# RF_wireless.net
KiCad netlist of a schematic drawn in Altium Designer
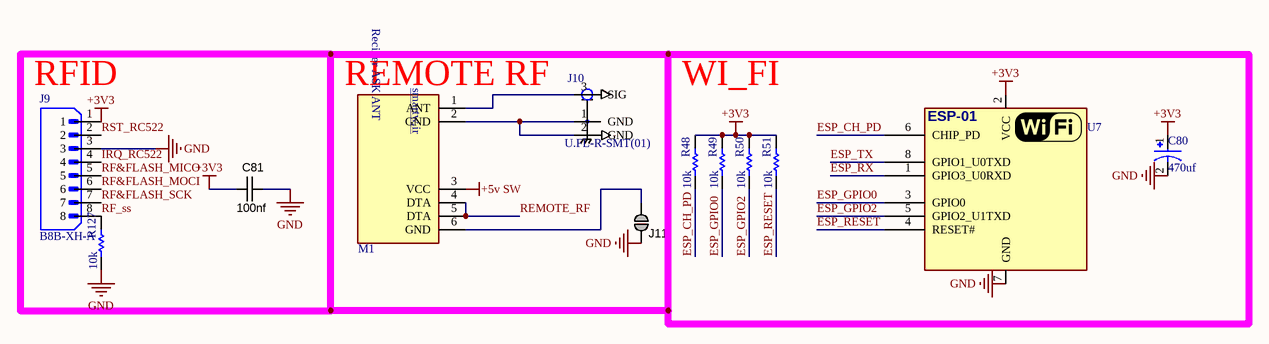
[diagram p0: RF & wireless.SchDoc]

(export (version "E")
  (design (tool "Eeschema 10.0.6"))
  (components
    (comp (ref "C80")
      (value "470uf")
      (footprint "CAP_4TPB330ML")
      (fields (field (name "MP") "4TPB330ML") (field (name "MF") "Sanyo Electric"))
      (libsource (lib "altium-import") (part "root_3_4TPB330ML_"))
    )
    (comp (ref "C81")
      (value "100nf")
      (footprint "CAPC1608X90N")
      (description "Capacitor SMD Cer 100nF 10% 50V X7R 0603")
      (fields (field (name "TOLERANCE") "±10%"))
      (libsource (lib "altium-import") (part "root_1_CAPC_100n_0603_X7R_50V_10%_"))
    )
    (comp (ref "J9")
      (value "B8B-XH-A")
      (footprint "JST_B8B-XH-A")
      (description "Connector Header Through Hole 8 position 0.098 (2.50mm)")
      (fields (field (name "MF") "JST"))
      (libsource (lib "B8B-XH-A") (part "B8B-XH-A"))
    )
    (comp (ref "J10")
      (value "U.FL-R-SMT(01)")
      (footprint "UFL")
      (description "U.FL Series 6 Ghz 50 Ohm Ultra-small SMT Coaxial Cable Receptacle")
      (fields (field (name "MF") "Hirose"))
      (libsource (lib "U.FL-R-SMT_01_") (part "U.FL-R-SMT(01)"))
    )
    (comp (ref "J11")
      (value "Jumper")
      (footprint "JUMP1")
      (description "SMD jumper")
      (libsource (lib "Utiliti_Library") (part "JUMP1"))
    )
    (comp (ref "M1")
      (value "ASK RF ANT 315/433MHZ")
      (footprint "RF_ETRXB")
      (libsource (lib "Module") (part "ASK RF ANT 315/433MHZ"))
    )
    (comp (ref "R48")
      (value "10k")
      (footprint "Resistor_SMD_0603 (1608)")
      (description "Resistor 0603")
      (fields (field (name "PUBLISHER") "Seyed Razi Vesali") (field (name "EMAIL") "razi.vesali@gmail.com"))
      (libsource (lib "resistors") (part "Resistor"))
    )
    (comp (ref "R49")
      (value "10k")
      (footprint "Resistor_SMD_0603 (1608)")
      (description "Resistor 0603")
      (fields (field (name "PUBLISHER") "Seyed Razi Vesali") (field (name "EMAIL") "razi.vesali@gmail.com"))
      (libsource (lib "resistors") (part "Resistor"))
    )
    (comp (ref "R50")
      (value "10k")
      (footprint "Resistor_SMD_0603 (1608)")
      (description "Resistor 0603")
      (fields (field (name "PUBLISHER") "Seyed Razi Vesali") (field (name "EMAIL") "razi.vesali@gmail.com"))
      (libsource (lib "resistors") (part "Resistor"))
    )
    (comp (ref "R51")
      (value "10k")
      (footprint "Resistor_SMD_0603 (1608)")
      (description "Resistor 0603")
      (fields (field (name "PUBLISHER") "Seyed Razi Vesali") (field (name "EMAIL") "razi.vesali@gmail.com"))
      (libsource (lib "resistors") (part "Resistor"))
    )
    (comp (ref "R127")
      (value "10k")
      (footprint "Resistor_SMD_0603 (1608)")
      (description "Resistor")
      (fields (field (name "PUBLISHER") "Seyed Razi Vesali") (field (name "EMAIL") "razi.vesali@gmail.com"))
      (libsource (lib "resistors") (part "Resistor"))
    )
    (comp (ref "U7")
      (value "ESP-01")
      (footprint "ESP8266_ESP01")
      (description "ESP8266 ESP-01 WiFi Module")
      (libsource (lib "altium-import") (part "root_0_ESP8266_ESP-01_"))
    )
  )
  (nets
    (net (code "1") (name "+3V3") (class "Default")
      (node (ref "C80") (pin "1") (pinfunction "1_1") (pintype "passive"))
      (node (ref "C81") (pin "1") (pintype "passive"))
      (node (ref "J9") (pin "1") (pinfunction "1_1") (pintype "passive"))
      (node (ref "R48") (pin "1") (pinfunction "1_1") (pintype "passive"))
      (node (ref "R49") (pin "1") (pinfunction "1_1") (pintype "passive"))
      (node (ref "R50") (pin "1") (pinfunction "1_1") (pintype "passive"))
      (node (ref "R51") (pin "1") (pinfunction "1_1") (pintype "passive"))
      (node (ref "U7") (pin "2") (pinfunction "VCC_2") (pintype "passive"))
    )
    (net (code "2") (name "+5v SW") (class "Default")
      (node (ref "M1") (pin "3") (pinfunction "VCC_3") (pintype "passive"))
    )
    (net (code "3") (name "/ESP_CH_PD") (class "Default")
      (node (ref "R48") (pin "2") (pinfunction "2_2") (pintype "passive"))
      (node (ref "U7") (pin "6") (pinfunction "CHIP_PD_6") (pintype "passive"))
    )
    (net (code "4") (name "/ESP_GPIO0") (class "Default")
      (node (ref "R49") (pin "2") (pinfunction "2_2") (pintype "passive"))
      (node (ref "U7") (pin "3") (pinfunction "GPIO0_3") (pintype "passive"))
    )
    (net (code "5") (name "/ESP_GPIO2") (class "Default")
      (node (ref "R50") (pin "2") (pinfunction "2_2") (pintype "passive"))
      (node (ref "U7") (pin "5") (pinfunction "GPIO2_U1TXD_5") (pintype "passive"))
    )
    (net (code "6") (name "/ESP_RESET") (class "Default")
      (node (ref "R51") (pin "2") (pinfunction "2_2") (pintype "passive"))
      (node (ref "U7") (pin "4") (pinfunction "RESET#_4") (pintype "passive"))
    )
    (net (code "7") (name "/ESP_RX") (class "Default")
      (node (ref "U7") (pin "1") (pinfunction "GPIO3_U0RXD_1") (pintype "passive"))
    )
    (net (code "8") (name "/ESP_TX") (class "Default")
      (node (ref "U7") (pin "8") (pinfunction "GPIO1_U0TXD_8") (pintype "passive"))
    )
    (net (code "9") (name "/IRQ_RC522") (class "Default")
      (node (ref "J9") (pin "4") (pinfunction "4_4") (pintype "passive"))
    )
    (net (code "10") (name "/REMOTE_RF") (class "Default")
      (node (ref "M1") (pin "4") (pinfunction "DTA_4") (pintype "passive"))
      (node (ref "M1") (pin "5") (pinfunction "DTA_5") (pintype "passive"))
    )
    (net (code "11") (name "/RF&FLASH_MICO") (class "Default")
      (node (ref "J9") (pin "5") (pinfunction "5_5") (pintype "passive"))
    )
    (net (code "12") (name "/RF&FLASH_MOCI") (class "Default")
      (node (ref "J9") (pin "6") (pinfunction "6_6") (pintype "passive"))
    )
    (net (code "13") (name "/RF&FLASH_SCK") (class "Default")
      (node (ref "J9") (pin "7") (pinfunction "7_7") (pintype "passive"))
    )
    (net (code "14") (name "/RF_ss") (class "Default")
      (node (ref "J9") (pin "8") (pinfunction "8_8") (pintype "passive"))
      (node (ref "R127") (pin "1") (pinfunction "1_1") (pintype "passive"))
    )
    (net (code "15") (name "/RST_RC522") (class "Default")
      (node (ref "J9") (pin "2") (pinfunction "2_2") (pintype "passive"))
    )
    (net (code "16") (name "GND") (class "Default")
      (node (ref "C80") (pin "2") (pinfunction "2_2") (pintype "passive"))
      (node (ref "C81") (pin "2") (pintype "passive"))
      (node (ref "J11") (pin "2") (pintype "passive"))
      (node (ref "J9") (pin "3") (pinfunction "3_3") (pintype "passive"))
      (node (ref "R127") (pin "2") (pinfunction "2_2") (pintype "passive"))
      (node (ref "U7") (pin "7") (pinfunction "GND_7") (pintype "passive"))
    )
    (net (code "17") (name "Net-(J10-GND-Pad1)") (class "Default")
      (node (ref "J10") (pin "1") (pinfunction "GND_1") (pintype "passive"))
      (node (ref "J10") (pin "2") (pinfunction "GND_2") (pintype "passive"))
      (node (ref "M1") (pin "2") (pinfunction "GND_2") (pintype "passive"))
    )
    (net (code "18") (name "Net-(J10-SIG)") (class "Default")
      (node (ref "J10") (pin "3") (pinfunction "SIG_3") (pintype "passive"))
      (node (ref "M1") (pin "1") (pinfunction "ANT_1") (pintype "passive"))
    )
    (net (code "19") (name "Net-(J11-Pad1)") (class "Default")
      (node (ref "J11") (pin "1") (pintype "passive"))
      (node (ref "M1") (pin "6") (pinfunction "GND_6") (pintype "passive"))
    )
  )
)
